# Circuit.net
KiCad netlist of a schematic drawn in EAGLE
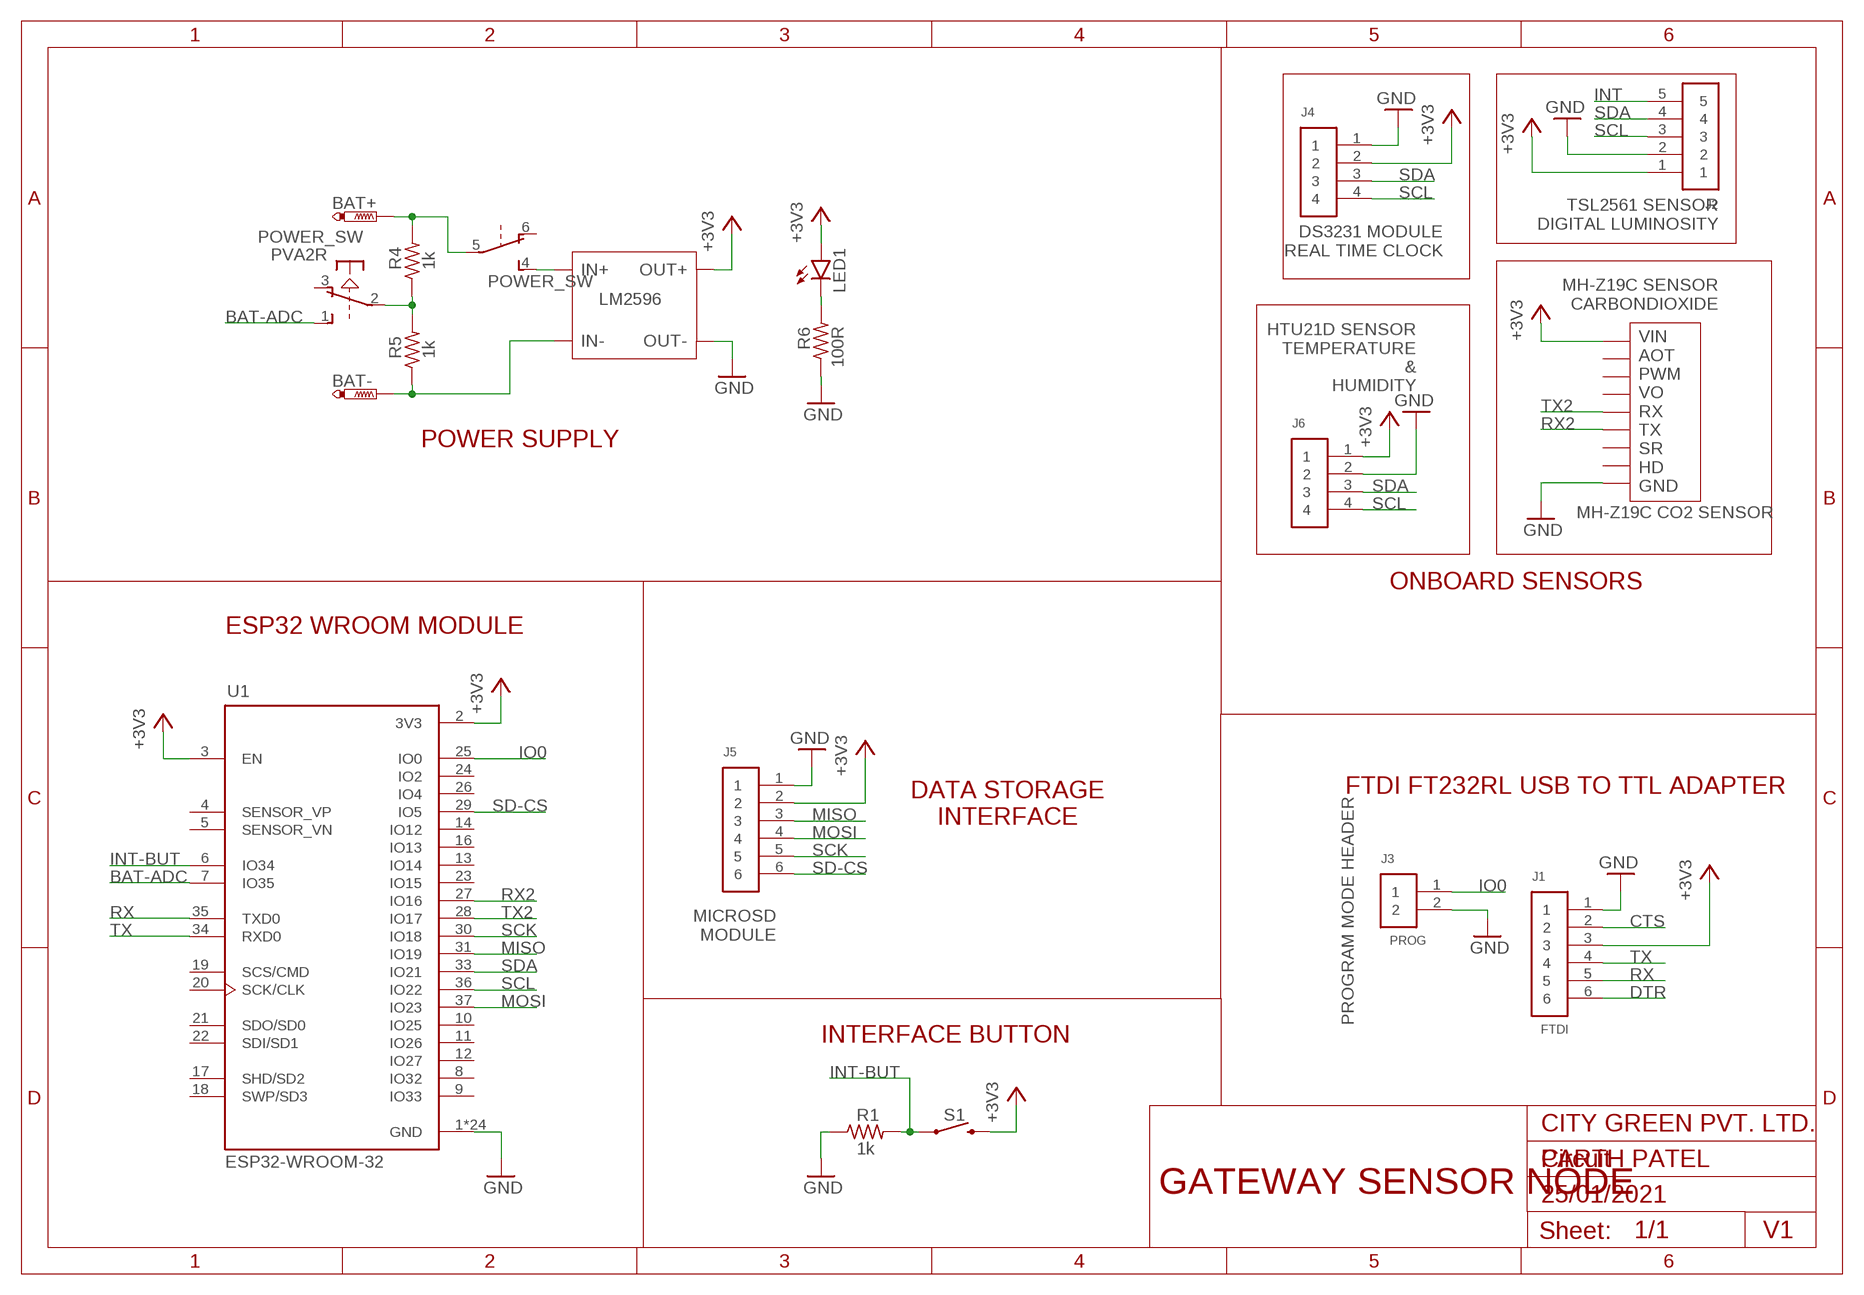
[diagram p0: schematic, sheet 1]

(export (version "E")
  (design (tool "Eeschema 10.0.6"))
  (components
    (comp (ref "BAT+")
      (value "PTR1TP20SQ")
      (footprint "eagle-import:TP20SQ")
      (libsource (lib "eagle-import") (part "PTR1TP20SQ"))
    )
    (comp (ref "BAT-")
      (value "PTR1TP20SQ")
      (footprint "eagle-import:TP20SQ")
      (libsource (lib "eagle-import") (part "PTR1TP20SQ"))
    )
    (comp (ref "J1")
      (value "FTDI")
      (footprint "eagle-import:61300611121")
      (fields
        (field (name "DIGI_KEY_PART_NUMBER") "732-5319-ND")
        (field (name "MANUFACTURER") "Wurth Electronics Inc.")
        (field (name "MPN") "61300611121")
        (field (name "CREATED_BY") "PCBLayout.com")
      )
      (libsource (lib "eagle-import") (part "61300611121"))
    )
    (comp (ref "J2")
      (value "TSL2561")
      (footprint "eagle-import:61300511121")
      (fields
        (field (name "DIGI_KEY_PART_NUMBER") "732-5318-ND")
        (field (name "MANUFACTURER") "Wurth Electronics Inc.")
        (field (name "MPN") "61300511121")
        (field (name "CREATED_BY") "PCBLayout.com")
      )
      (libsource (lib "eagle-import") (part "61300511121"))
    )
    (comp (ref "J3")
      (value "PROG")
      (footprint "eagle-import:61300211121")
      (fields
        (field (name "DIGI_KEY_PART_NUMBER") "732-5315-ND")
        (field (name "MANUFACTURER") "Wurth Electronics Inc.")
        (field (name "MPN") "61300211121")
        (field (name "CREATED_BY") "PCBLayout.com")
      )
      (libsource (lib "eagle-import") (part "61300211121"))
    )
    (comp (ref "J4")
      (value "DS3231")
      (footprint "eagle-import:61300411121")
      (fields
        (field (name "DIGI_KEY_PART_NUMBER") "732-5317-ND")
        (field (name "MANUFACTURER") "Wurth Electronics Inc.")
        (field (name "MPN") "61300411121")
        (field (name "CREATED_BY") "PCBLayout.com")
      )
      (libsource (lib "eagle-import") (part "61300411121"))
    )
    (comp (ref "J5")
      (value "MicroSD")
      (footprint "eagle-import:61300611121")
      (fields
        (field (name "DIGI_KEY_PART_NUMBER") "732-5319-ND")
        (field (name "MANUFACTURER") "Wurth Electronics Inc.")
        (field (name "MPN") "61300611121")
        (field (name "CREATED_BY") "PCBLayout.com")
      )
      (libsource (lib "eagle-import") (part "61300611121"))
    )
    (comp (ref "J6")
      (value "HTU21D")
      (footprint "eagle-import:61300411121")
      (fields
        (field (name "DIGI_KEY_PART_NUMBER") "732-5317-ND")
        (field (name "MANUFACTURER") "Wurth Electronics Inc.")
        (field (name "MPN") "61300411121")
        (field (name "CREATED_BY") "PCBLayout.com")
      )
      (libsource (lib "eagle-import") (part "61300411121"))
    )
    (comp (ref "LED1")
      (value "LED3MM")
      (footprint "eagle-import:LED3MM")
      (libsource (lib "eagle-import") (part "LED3MM"))
    )
    (comp (ref "POWER_SW")
      (value "PVA2R")
      (footprint "eagle-import:PVA2R")
      (libsource (lib "eagle-import") (part "PVA2R"))
    )
    (comp (ref "R1")
      (value "1k")
      (footprint "eagle-import:0204_7")
      (libsource (lib "eagle-import") (part "R-US_0204/7"))
    )
    (comp (ref "R4")
      (value "1k")
      (footprint "eagle-import:0204_7")
      (libsource (lib "eagle-import") (part "R-US_0204/7"))
    )
    (comp (ref "R5")
      (value "1k")
      (footprint "eagle-import:0204_7")
      (libsource (lib "eagle-import") (part "R-US_0204/7"))
    )
    (comp (ref "R6")
      (value "100R")
      (footprint "eagle-import:0204_7")
      (libsource (lib "eagle-import") (part "R-US_0204/7"))
    )
    (comp (ref "S1")
      (value "MOMENTARY-SWITCH-SPST-PTH-6.0MM")
      (footprint "eagle-import:TACTILE_SWITCH_PTH_6.0MM")
      (libsource (lib "eagle-import") (part "MOMENTARY-SWITCH-SPST-PTH-6.0MM"))
    )
    (comp (ref "U$1")
      (value "MH-Z19C")
      (footprint "eagle-import:MH-Z19C")
      (libsource (lib "eagle-import") (part "MH-Z19C"))
    )
    (comp (ref "U$2")
      (value "XL6009")
      (footprint "eagle-import:XL6009")
      (libsource (lib "eagle-import") (part "XL6009"))
    )
    (comp (ref "U1")
      (value "ESP32-WROOM-32")
      (footprint "eagle-import:MODULE_ESP32-WROOM-32")
      (fields (field (name "MF") "Espressif Systems"))
      (libsource (lib "eagle-import") (part "ESP32-WROOM-32"))
    )
  )
  (nets
    (net (code "1") (name "+3V3") (class "Default")
      (node (ref "J1") (pin "3") (pinfunction "3_3") (pintype "passive"))
      (node (ref "J2") (pin "1") (pinfunction "1_1") (pintype "passive"))
      (node (ref "J4") (pin "2") (pinfunction "2_2") (pintype "passive"))
      (node (ref "J5") (pin "2") (pinfunction "2_2") (pintype "passive"))
      (node (ref "J6") (pin "1") (pinfunction "1_1") (pintype "passive"))
      (node (ref "LED1") (pin "A") (pinfunction "A_A") (pintype "passive"))
      (node (ref "S1") (pin "3") (pinfunction "2_3") (pintype "passive"))
      (node (ref "U$1") (pin "PWM") (pinfunction "VIN_PWM") (pintype "bidirectional"))
      (node (ref "U$2") (pin "OUT+") (pinfunction "OUT+_OUT+") (pintype "bidirectional"))
      (node (ref "U1") (pin "2") (pinfunction "3V3_2") (pintype "power_in"))
      (node (ref "U1") (pin "3") (pinfunction "EN_3") (pintype "input"))
    )
    (net (code "2") (name "/BAT-ADC") (class "Default")
      (node (ref "POWER_SW") (pin "1") (pinfunction "S_1") (pintype "passive"))
      (node (ref "U1") (pin "7") (pinfunction "IO35_7") (pintype "input"))
    )
    (net (code "3") (name "/CTS") (class "Default")
      (node (ref "J1") (pin "2") (pinfunction "2_2") (pintype "passive"))
    )
    (net (code "4") (name "/DTR") (class "Default")
      (node (ref "J1") (pin "6") (pinfunction "6_6") (pintype "passive"))
    )
    (net (code "5") (name "/INT") (class "Default")
      (node (ref "J2") (pin "5") (pinfunction "5_5") (pintype "passive"))
    )
    (net (code "6") (name "/INT-BUT") (class "Default")
      (node (ref "R1") (pin "2") (pinfunction "2_2") (pintype "passive"))
      (node (ref "S1") (pin "1") (pinfunction "1_1") (pintype "passive"))
      (node (ref "U1") (pin "6") (pinfunction "IO34_6") (pintype "input"))
    )
    (net (code "7") (name "/IO0") (class "Default")
      (node (ref "J3") (pin "1") (pinfunction "1_1") (pintype "passive"))
      (node (ref "U1") (pin "25") (pinfunction "IO0_25") (pintype "bidirectional"))
    )
    (net (code "8") (name "/MISO") (class "Default")
      (node (ref "J5") (pin "3") (pinfunction "3_3") (pintype "passive"))
      (node (ref "U1") (pin "31") (pinfunction "IO19_31") (pintype "bidirectional"))
    )
    (net (code "9") (name "/MOSI") (class "Default")
      (node (ref "J5") (pin "4") (pinfunction "4_4") (pintype "passive"))
      (node (ref "U1") (pin "37") (pinfunction "IO23_37") (pintype "bidirectional"))
    )
    (net (code "10") (name "/RX") (class "Default")
      (node (ref "J1") (pin "5") (pinfunction "5_5") (pintype "passive"))
      (node (ref "U1") (pin "35") (pinfunction "TXD0_35") (pintype "bidirectional"))
    )
    (net (code "11") (name "/RX2") (class "Default")
      (node (ref "U$1") (pin "TX") (pinfunction "TX_TX") (pintype "bidirectional"))
      (node (ref "U1") (pin "27") (pinfunction "IO16_27") (pintype "bidirectional"))
    )
    (net (code "12") (name "/SCK") (class "Default")
      (node (ref "J5") (pin "5") (pinfunction "5_5") (pintype "passive"))
      (node (ref "U1") (pin "30") (pinfunction "IO18_30") (pintype "bidirectional"))
    )
    (net (code "13") (name "/SCL") (class "Default")
      (node (ref "J2") (pin "3") (pinfunction "3_3") (pintype "passive"))
      (node (ref "J4") (pin "4") (pinfunction "4_4") (pintype "passive"))
      (node (ref "J6") (pin "4") (pinfunction "4_4") (pintype "passive"))
      (node (ref "U1") (pin "36") (pinfunction "IO22_36") (pintype "bidirectional"))
    )
    (net (code "14") (name "/SD-CS") (class "Default")
      (node (ref "J5") (pin "6") (pinfunction "6_6") (pintype "passive"))
      (node (ref "U1") (pin "29") (pinfunction "IO5_29") (pintype "bidirectional"))
    )
    (net (code "15") (name "/SDA") (class "Default")
      (node (ref "J2") (pin "4") (pinfunction "4_4") (pintype "passive"))
      (node (ref "J4") (pin "3") (pinfunction "3_3") (pintype "passive"))
      (node (ref "J6") (pin "3") (pinfunction "3_3") (pintype "passive"))
      (node (ref "U1") (pin "33") (pinfunction "IO21_33") (pintype "bidirectional"))
    )
    (net (code "16") (name "/TX") (class "Default")
      (node (ref "J1") (pin "4") (pinfunction "4_4") (pintype "passive"))
      (node (ref "U1") (pin "34") (pinfunction "RXD0_34") (pintype "bidirectional"))
    )
    (net (code "17") (name "/TX2") (class "Default")
      (node (ref "U$1") (pin "SR") (pinfunction "RX_SR") (pintype "bidirectional"))
      (node (ref "U1") (pin "28") (pinfunction "IO17_28") (pintype "bidirectional"))
    )
    (net (code "18") (name "GND") (class "Default")
      (node (ref "J1") (pin "1") (pinfunction "1_1") (pintype "passive"))
      (node (ref "J2") (pin "2") (pinfunction "2_2") (pintype "passive"))
      (node (ref "J3") (pin "2") (pinfunction "2_2") (pintype "passive"))
      (node (ref "J4") (pin "1") (pinfunction "1_1") (pintype "passive"))
      (node (ref "J5") (pin "1") (pinfunction "1_1") (pintype "passive"))
      (node (ref "J6") (pin "2") (pinfunction "2_2") (pintype "passive"))
      (node (ref "R1") (pin "1") (pinfunction "1_1") (pintype "passive"))
      (node (ref "R6") (pin "1") (pinfunction "1_1") (pintype "passive"))
      (node (ref "U$1") (pin "AOT") (pinfunction "GND_AOT") (pintype "bidirectional"))
      (node (ref "U$2") (pin "OUT-") (pinfunction "OUT-_OUT-") (pintype "bidirectional"))
      (node (ref "U1") (pin "1") (pinfunction "GND_1") (pintype "power_in"))
      (node (ref "U1") (pin "15") (pinfunction "GND_15") (pintype "power_in"))
      (node (ref "U1") (pin "38") (pinfunction "GND_38") (pintype "power_in"))
      (node (ref "U1") (pin "39_1") (pinfunction "GND_39_1") (pintype "power_in"))
      (node (ref "U1") (pin "39_10") (pinfunction "GND_39_10") (pintype "power_in"))
      (node (ref "U1") (pin "39_11") (pinfunction "GND_39_11") (pintype "power_in"))
      (node (ref "U1") (pin "39_12") (pinfunction "GND_39_12") (pintype "power_in"))
      (node (ref "U1") (pin "39_13") (pinfunction "GND_39_13") (pintype "power_in"))
      (node (ref "U1") (pin "39_14") (pinfunction "GND_39_14") (pintype "power_in"))
      (node (ref "U1") (pin "39_15") (pinfunction "GND_39_15") (pintype "power_in"))
      (node (ref "U1") (pin "39_16") (pinfunction "GND_39_16") (pintype "power_in"))
      (node (ref "U1") (pin "39_17") (pinfunction "GND_39_17") (pintype "power_in"))
      (node (ref "U1") (pin "39_18") (pinfunction "GND_39_18") (pintype "power_in"))
      (node (ref "U1") (pin "39_19") (pinfunction "GND_39_19") (pintype "power_in"))
      (node (ref "U1") (pin "39_2") (pinfunction "GND_39_2") (pintype "power_in"))
      (node (ref "U1") (pin "39_20") (pinfunction "GND_39_20") (pintype "power_in"))
      (node (ref "U1") (pin "39_21") (pinfunction "GND_39_21") (pintype "power_in"))
      (node (ref "U1") (pin "39_3") (pinfunction "GND_39_3") (pintype "power_in"))
      (node (ref "U1") (pin "39_4") (pinfunction "GND_39_4") (pintype "power_in"))
      (node (ref "U1") (pin "39_5") (pinfunction "GND_39_5") (pintype "power_in"))
      (node (ref "U1") (pin "39_6") (pinfunction "GND_39_6") (pintype "power_in"))
      (node (ref "U1") (pin "39_7") (pinfunction "GND_39_7") (pintype "power_in"))
      (node (ref "U1") (pin "39_8") (pinfunction "GND_39_8") (pintype "power_in"))
      (node (ref "U1") (pin "39_9") (pinfunction "GND_39_9") (pintype "power_in"))
    )
    (net (code "19") (name "Net-(BAT--PadTP)") (class "Default")
      (node (ref "BAT-") (pin "TP") (pinfunction "TP_TP") (pintype "input"))
      (node (ref "R5") (pin "1") (pinfunction "1_1") (pintype "passive"))
      (node (ref "U$2") (pin "IN-") (pinfunction "IN-_IN-") (pintype "bidirectional"))
    )
    (net (code "20") (name "Net-(LED1-C)") (class "Default")
      (node (ref "LED1") (pin "K") (pinfunction "C_K") (pintype "passive"))
      (node (ref "R6") (pin "2") (pinfunction "2_2") (pintype "passive"))
    )
    (net (code "21") (name "Net-(POWER_SWA-P)") (class "Default")
      (node (ref "POWER_SW") (pin "2") (pinfunction "P_2") (pintype "passive"))
      (node (ref "R4") (pin "1") (pinfunction "1_1") (pintype "passive"))
      (node (ref "R5") (pin "2") (pinfunction "2_2") (pintype "passive"))
    )
    (net (code "22") (name "Net-(POWER_SWB-P)") (class "Default")
      (node (ref "BAT+") (pin "TP") (pinfunction "TP_TP") (pintype "input"))
      (node (ref "POWER_SW") (pin "5") (pinfunction "P_5") (pintype "passive"))
      (node (ref "R4") (pin "2") (pinfunction "2_2") (pintype "passive"))
    )
    (net (code "23") (name "Net-(POWER_SWB-S)") (class "Default")
      (node (ref "POWER_SW") (pin "4") (pinfunction "S_4") (pintype "passive"))
      (node (ref "U$2") (pin "IN+") (pinfunction "IN+_IN+") (pintype "bidirectional"))
    )
    (net (code "24") (name "unconnected-(POWER_SWA-O-Pad3)") (class "Default")
      (node (ref "POWER_SW") (pin "3") (pinfunction "O_3") (pintype "passive"))
    )
    (net (code "25") (name "unconnected-(POWER_SWB-O-Pad6)") (class "Default")
      (node (ref "POWER_SW") (pin "6") (pinfunction "O_6") (pintype "passive"))
    )
    (net (code "26") (name "unconnected-(U$1-AOT-PadGND)") (class "Default")
      (node (ref "U$1") (pin "GND") (pinfunction "AOT_GND") (pintype "bidirectional"))
    )
    (net (code "27") (name "unconnected-(U$1-HD-PadVO)") (class "Default")
      (node (ref "U$1") (pin "VO") (pinfunction "HD_VO") (pintype "bidirectional"))
    )
    (net (code "28") (name "unconnected-(U$1-PWM-PadVIN)") (class "Default")
      (node (ref "U$1") (pin "VIN") (pinfunction "PWM_VIN") (pintype "bidirectional"))
    )
    (net (code "29") (name "unconnected-(U$1-SR-PadRX)") (class "Default")
      (node (ref "U$1") (pin "RX") (pinfunction "SR_RX") (pintype "bidirectional"))
    )
    (net (code "30") (name "unconnected-(U$1-VO-PadHD)") (class "Default")
      (node (ref "U$1") (pin "HD") (pinfunction "VO_HD") (pintype "bidirectional"))
    )
    (net (code "31") (name "unconnected-(U1-IO2-Pad24)") (class "Default")
      (node (ref "U1") (pin "24") (pinfunction "IO2_24") (pintype "bidirectional"))
    )
    (net (code "32") (name "unconnected-(U1-IO4-Pad26)") (class "Default")
      (node (ref "U1") (pin "26") (pinfunction "IO4_26") (pintype "bidirectional"))
    )
    (net (code "33") (name "unconnected-(U1-IO12-Pad14)") (class "Default")
      (node (ref "U1") (pin "14") (pinfunction "IO12_14") (pintype "bidirectional"))
    )
    (net (code "34") (name "unconnected-(U1-IO13-Pad16)") (class "Default")
      (node (ref "U1") (pin "16") (pinfunction "IO13_16") (pintype "bidirectional"))
    )
    (net (code "35") (name "unconnected-(U1-IO14-Pad13)") (class "Default")
      (node (ref "U1") (pin "13") (pinfunction "IO14_13") (pintype "bidirectional"))
    )
    (net (code "36") (name "unconnected-(U1-IO15-Pad23)") (class "Default")
      (node (ref "U1") (pin "23") (pinfunction "IO15_23") (pintype "bidirectional"))
    )
    (net (code "37") (name "unconnected-(U1-IO25-Pad10)") (class "Default")
      (node (ref "U1") (pin "10") (pinfunction "IO25_10") (pintype "bidirectional"))
    )
    (net (code "38") (name "unconnected-(U1-IO26-Pad11)") (class "Default")
      (node (ref "U1") (pin "11") (pinfunction "IO26_11") (pintype "bidirectional"))
    )
    (net (code "39") (name "unconnected-(U1-IO27-Pad12)") (class "Default")
      (node (ref "U1") (pin "12") (pinfunction "IO27_12") (pintype "bidirectional"))
    )
    (net (code "40") (name "unconnected-(U1-IO32-Pad8)") (class "Default")
      (node (ref "U1") (pin "8") (pinfunction "IO32_8") (pintype "bidirectional"))
    )
    (net (code "41") (name "unconnected-(U1-IO33-Pad9)") (class "Default")
      (node (ref "U1") (pin "9") (pinfunction "IO33_9") (pintype "bidirectional"))
    )
    (net (code "42") (name "unconnected-(U1-SCK{slash}CLK-Pad20)") (class "Default")
      (node (ref "U1") (pin "20") (pinfunction "SCK/CLK_20") (pintype "bidirectional"))
    )
    (net (code "43") (name "unconnected-(U1-SCS{slash}CMD-Pad19)") (class "Default")
      (node (ref "U1") (pin "19") (pinfunction "SCS/CMD_19") (pintype "bidirectional"))
    )
    (net (code "44") (name "unconnected-(U1-SDI{slash}SD1-Pad22)") (class "Default")
      (node (ref "U1") (pin "22") (pinfunction "SDI/SD1_22") (pintype "bidirectional"))
    )
    (net (code "45") (name "unconnected-(U1-SDO{slash}SD0-Pad21)") (class "Default")
      (node (ref "U1") (pin "21") (pinfunction "SDO/SD0_21") (pintype "bidirectional"))
    )
    (net (code "46") (name "unconnected-(U1-SENSOR_VN-Pad5)") (class "Default")
      (node (ref "U1") (pin "5") (pinfunction "SENSOR_VN_5") (pintype "input"))
    )
    (net (code "47") (name "unconnected-(U1-SENSOR_VP-Pad4)") (class "Default")
      (node (ref "U1") (pin "4") (pinfunction "SENSOR_VP_4") (pintype "input"))
    )
    (net (code "48") (name "unconnected-(U1-SHD{slash}SD2-Pad17)") (class "Default")
      (node (ref "U1") (pin "17") (pinfunction "SHD/SD2_17") (pintype "bidirectional"))
    )
    (net (code "49") (name "unconnected-(U1-SWP{slash}SD3-Pad18)") (class "Default")
      (node (ref "U1") (pin "18") (pinfunction "SWP/SD3_18") (pintype "bidirectional"))
    )
  )
)
